# Payload_Computer.net
KiCad netlist of a schematic drawn in EAGLE
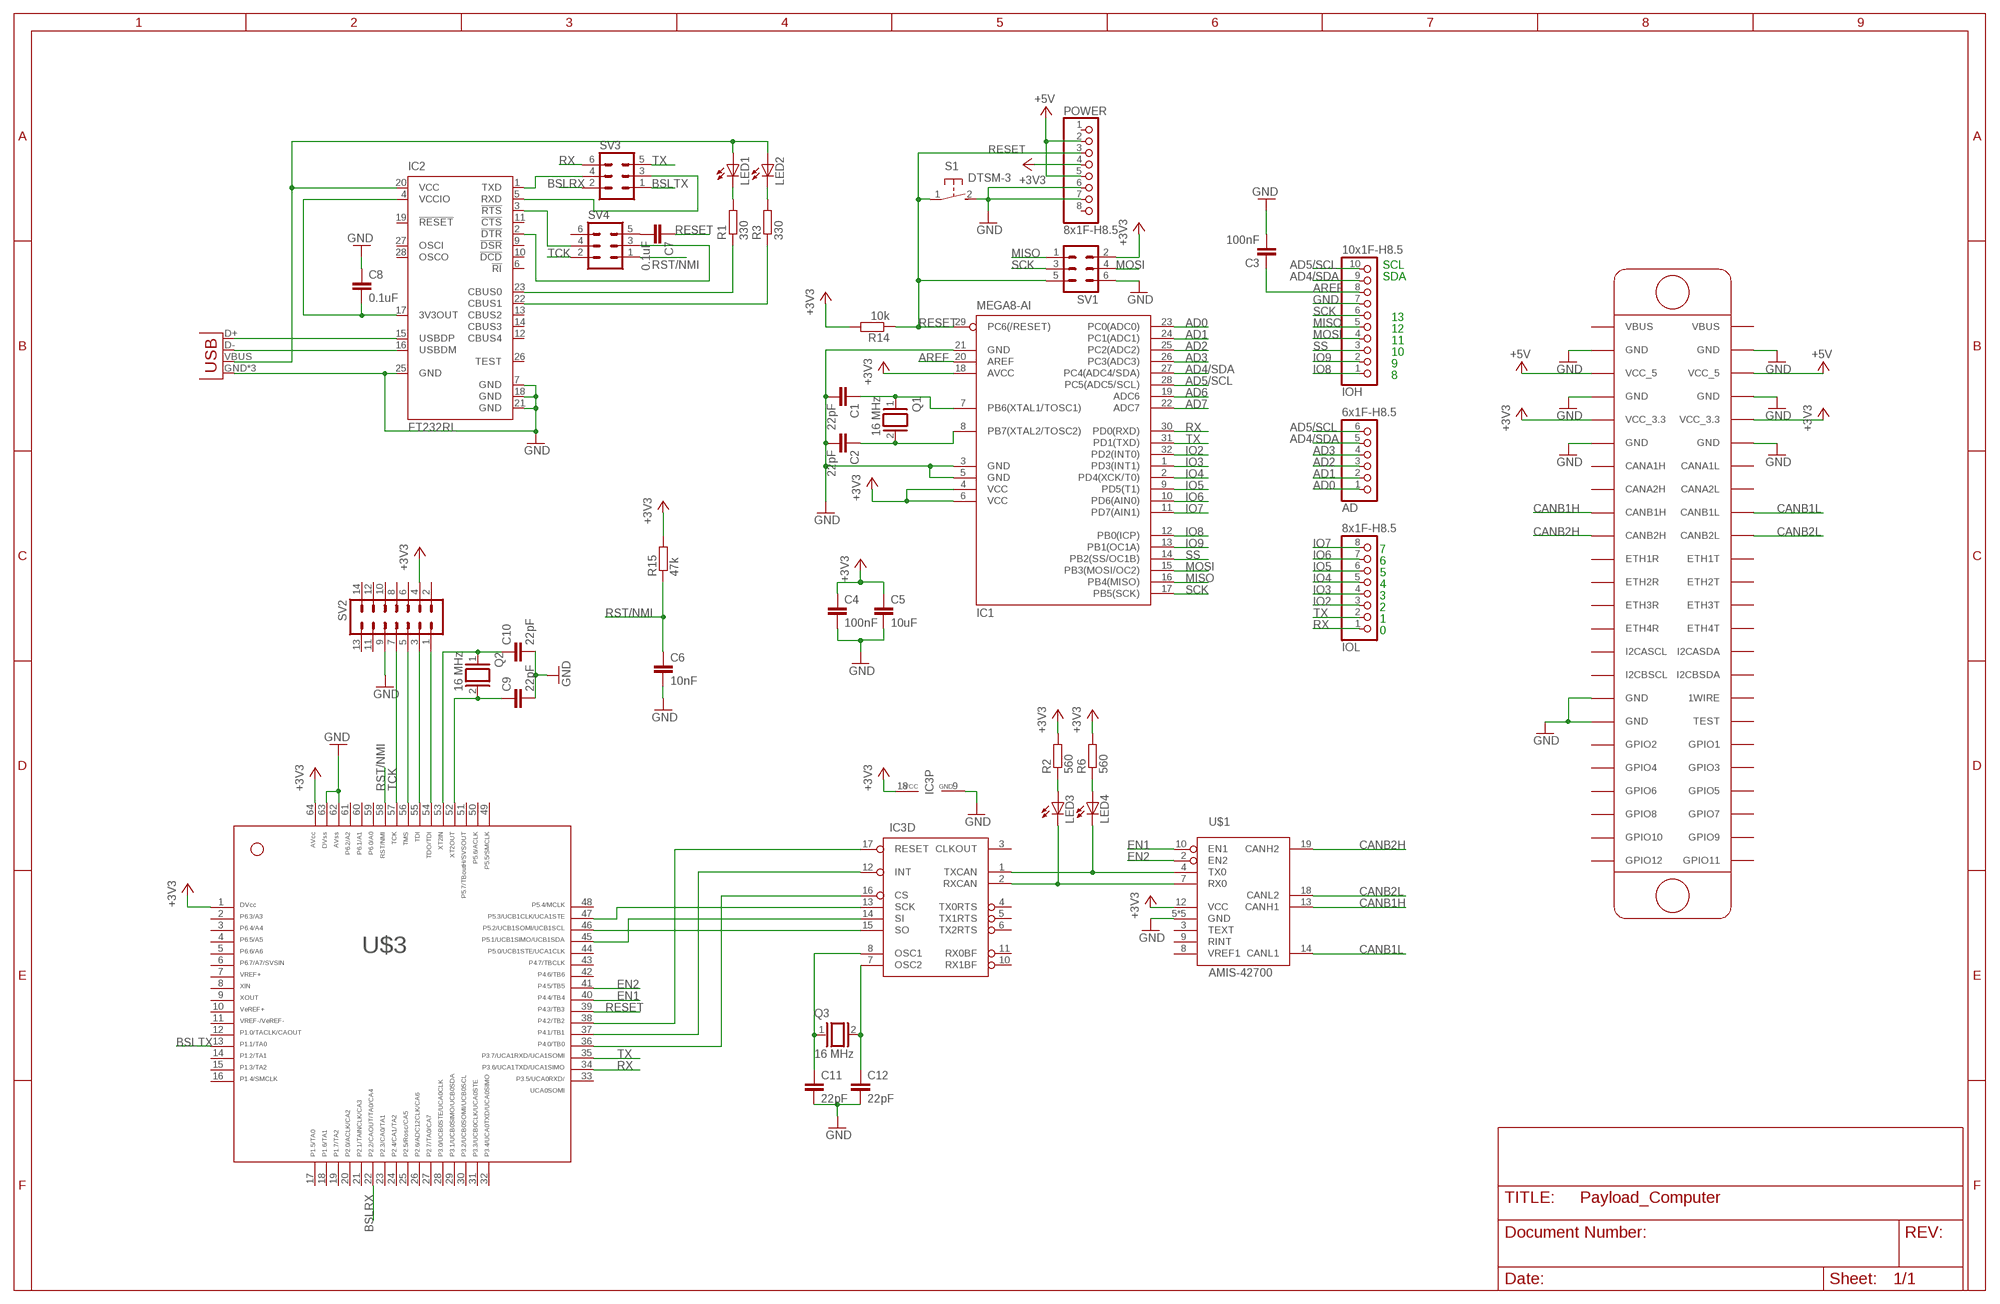
[diagram p0: schematic, sheet 1]

(export (version "E")
  (design (tool "Eeschema 10.0.6"))
  (components
    (comp (ref "AD")
      (value "6x1F-H8.5")
      (footprint "eagle-import:1X06")
      (libsource (lib "eagle-import") (part "PINHD-1X6"))
    )
    (comp (ref "C1")
      (value "22pF")
      (footprint "eagle-import:C0805")
      (libsource (lib "eagle-import") (part "C-EUC0805"))
    )
    (comp (ref "C2")
      (value "22pF")
      (footprint "eagle-import:C0805")
      (libsource (lib "eagle-import") (part "C-EUC0805"))
    )
    (comp (ref "C3")
      (value "100nF")
      (footprint "eagle-import:C0805")
      (libsource (lib "eagle-import") (part "C-EUC0805"))
    )
    (comp (ref "C4")
      (value "100nF")
      (footprint "eagle-import:C0805")
      (libsource (lib "eagle-import") (part "C-EUC0805"))
    )
    (comp (ref "C5")
      (value "10uF")
      (footprint "eagle-import:C0805")
      (libsource (lib "eagle-import") (part "C-EUC0805"))
    )
    (comp (ref "C6")
      (value "10nF")
      (footprint "eagle-import:C0805")
      (libsource (lib "eagle-import") (part "C-EUC0805"))
    )
    (comp (ref "C7")
      (value "0.1uF")
      (footprint "eagle-import:C0805")
      (libsource (lib "eagle-import") (part "C-EUC0805"))
    )
    (comp (ref "C8")
      (value "0.1uF")
      (footprint "eagle-import:C0805")
      (libsource (lib "eagle-import") (part "C-EUC0805"))
    )
    (comp (ref "C9")
      (value "22pF")
      (footprint "eagle-import:C0805")
      (libsource (lib "eagle-import") (part "C-EUC0805"))
    )
    (comp (ref "C10")
      (value "22pF")
      (footprint "eagle-import:C0805")
      (libsource (lib "eagle-import") (part "C-EUC0805"))
    )
    (comp (ref "C11")
      (value "22pF")
      (footprint "eagle-import:C0805")
      (libsource (lib "eagle-import") (part "C-EUC0805"))
    )
    (comp (ref "C12")
      (value "22pF")
      (footprint "eagle-import:C0805")
      (libsource (lib "eagle-import") (part "C-EUC0805"))
    )
    (comp (ref "IC1")
      (value "MEGA8-AI")
      (footprint "eagle-import:TQFP32-08")
      (fields (field (name "MPN") "ATMEGA8-16AU"))
      (libsource (lib "eagle-import") (part "MEGA8-AI"))
    )
    (comp (ref "IC2")
      (value "FT232RL")
      (footprint "eagle-import:SSOP28")
      (libsource (lib "eagle-import") (part "FT232RL"))
    )
    (comp (ref "IC3")
      (value "MCP2515SO")
      (footprint "eagle-import:SO-18W")
      (libsource (lib "eagle-import") (part "MCP2515SO"))
    )
    (comp (ref "IOH")
      (value "10x1F-H8.5")
      (footprint "eagle-import:1X10")
      (libsource (lib "eagle-import") (part "PINHD-1X10_ARD"))
    )
    (comp (ref "IOL")
      (value "8x1F-H8.5")
      (footprint "eagle-import:1X08")
      (libsource (lib "eagle-import") (part "PINHD-1X8"))
    )
    (comp (ref "JP1")
      (value "USB-MICROB")
      (footprint "eagle-import:USB-MICROB")
      (libsource (lib "eagle-import") (part "USB-MICROB"))
    )
    (comp (ref "LED1")
      (value "LED3MM")
      (footprint "eagle-import:LED3MM")
      (libsource (lib "eagle-import") (part "LED3MM"))
    )
    (comp (ref "LED2")
      (value "LED3MM")
      (footprint "eagle-import:LED3MM")
      (libsource (lib "eagle-import") (part "LED3MM"))
    )
    (comp (ref "LED3")
      (value "LED3MM")
      (footprint "eagle-import:LED3MM")
      (libsource (lib "eagle-import") (part "LED3MM"))
    )
    (comp (ref "LED4")
      (value "LED3MM")
      (footprint "eagle-import:LED3MM")
      (libsource (lib "eagle-import") (part "LED3MM"))
    )
    (comp (ref "POWER")
      (value "8x1F-H8.5")
      (footprint "eagle-import:1X08")
      (libsource (lib "eagle-import") (part "PINHD-1X8"))
    )
    (comp (ref "Q1")
      (value "16 MHz")
      (footprint "eagle-import:QS")
      (libsource (lib "eagle-import") (part "XTAL/S"))
    )
    (comp (ref "Q2")
      (value "16 MHz")
      (footprint "eagle-import:QS")
      (libsource (lib "eagle-import") (part "XTAL/S"))
    )
    (comp (ref "Q3")
      (value "16 MHz")
      (footprint "eagle-import:QS")
      (libsource (lib "eagle-import") (part "XTAL/S"))
    )
    (comp (ref "R1")
      (value "330")
      (footprint "eagle-import:R0805")
      (libsource (lib "eagle-import") (part "R-EU_R0805"))
    )
    (comp (ref "R2")
      (value "560")
      (footprint "eagle-import:R0805")
      (libsource (lib "eagle-import") (part "R-EU_R0805"))
    )
    (comp (ref "R3")
      (value "330")
      (footprint "eagle-import:R0805")
      (libsource (lib "eagle-import") (part "R-EU_R0805"))
    )
    (comp (ref "R6")
      (value "560")
      (footprint "eagle-import:R0805")
      (libsource (lib "eagle-import") (part "R-EU_R0805"))
    )
    (comp (ref "R14")
      (value "10k")
      (footprint "eagle-import:R0805")
      (libsource (lib "eagle-import") (part "R-EU_R0805"))
    )
    (comp (ref "R15")
      (value "47k")
      (footprint "eagle-import:R0805")
      (libsource (lib "eagle-import") (part "R-EU_R0805"))
    )
    (comp (ref "S1")
      (value "DTSM-3")
      (footprint "eagle-import:DTSM-3")
      (libsource (lib "eagle-import") (part "DTSM-3"))
    )
    (comp (ref "SV1")
      (value "MA03-2")
      (footprint "eagle-import:MA03-2")
      (libsource (lib "eagle-import") (part "MA03-2"))
    )
    (comp (ref "SV2")
      (value "MA07-2")
      (footprint "eagle-import:MA07-2")
      (libsource (lib "eagle-import") (part "MA07-2"))
    )
    (comp (ref "SV3")
      (value "MA03-2")
      (footprint "eagle-import:MA03-2")
      (libsource (lib "eagle-import") (part "MA03-2"))
    )
    (comp (ref "SV4")
      (value "MA03-2")
      (footprint "eagle-import:MA03-2")
      (libsource (lib "eagle-import") (part "MA03-2"))
    )
    (comp (ref "U$1")
      (value "AMIS-42700")
      (footprint "eagle-import:SOIC20")
      (libsource (lib "eagle-import") (part "AMIS-42700"))
    )
    (comp (ref "U$2")
      (value "CUBESAT_PCB")
      (footprint "eagle-import:CUBESAT_PCB")
      (libsource (lib "eagle-import") (part "CUBESAT_PCB"))
    )
    (comp (ref "U$3")
      (value "F241X---PM64")
      (footprint "eagle-import:PM_PAG64")
      (libsource (lib "eagle-import") (part "F241X---PM64"))
    )
  )
  (nets
    (net (code "1") (name "+3V3") (class "Default")
      (node (ref "C4") (pin "1") (pinfunction "1_1") (pintype "passive"))
      (node (ref "C5") (pin "1") (pinfunction "1_1") (pintype "passive"))
      (node (ref "IC1") (pin "18") (pinfunction "AVCC_18") (pintype "power_in"))
      (node (ref "IC1") (pin "4") (pinfunction "VCC_4") (pintype "power_in"))
      (node (ref "IC1") (pin "6") (pinfunction "VCC_6") (pintype "power_in"))
      (node (ref "IC3") (pin "18") (pinfunction "VCC_18") (pintype "power_in"))
      (node (ref "POWER") (pin "4") (pinfunction "4_4") (pintype "passive"))
      (node (ref "R14") (pin "2") (pinfunction "2_2") (pintype "passive"))
      (node (ref "R15") (pin "2") (pinfunction "2_2") (pintype "passive"))
      (node (ref "R2") (pin "2") (pinfunction "2_2") (pintype "passive"))
      (node (ref "R6") (pin "2") (pinfunction "2_2") (pintype "passive"))
      (node (ref "SV1") (pin "2") (pinfunction "2_2") (pintype "passive"))
      (node (ref "SV2") (pin "4") (pinfunction "4_4") (pintype "passive"))
      (node (ref "U$1") (pin "12") (pinfunction "VCC_12") (pintype "power_in"))
      (node (ref "U$2") (pin "VCC_3.3@1") (pinfunction "VCC_3.3_VCC_3.3@1") (pintype "bidirectional"))
      (node (ref "U$2") (pin "VCC_3.3@2") (pinfunction "VCC_3.3_VCC_3.3@2") (pintype "bidirectional"))
      (node (ref "U$3") (pin "1") (pinfunction "1_1") (pintype "power_in"))
      (node (ref "U$3") (pin "64") (pinfunction "64_64") (pintype "power_in"))
    )
    (net (code "2") (name "+5V") (class "Default")
      (node (ref "POWER") (pin "2") (pinfunction "2_2") (pintype "passive"))
      (node (ref "POWER") (pin "5") (pinfunction "5_5") (pintype "passive"))
      (node (ref "U$2") (pin "VCC_5@1") (pinfunction "VCC_5_VCC_5@1") (pintype "bidirectional"))
      (node (ref "U$2") (pin "VCC_5@2") (pinfunction "VCC_5_VCC_5@2") (pintype "bidirectional"))
    )
    (net (code "3") (name "/AD0") (class "Default")
      (node (ref "AD") (pin "1") (pinfunction "1_1") (pintype "passive"))
      (node (ref "IC1") (pin "23") (pinfunction "PC0(ADC0)_23") (pintype "bidirectional"))
    )
    (net (code "4") (name "/AD1") (class "Default")
      (node (ref "AD") (pin "2") (pinfunction "2_2") (pintype "passive"))
      (node (ref "IC1") (pin "24") (pinfunction "PC1(ADC1)_24") (pintype "bidirectional"))
    )
    (net (code "5") (name "/AD2") (class "Default")
      (node (ref "AD") (pin "3") (pinfunction "3_3") (pintype "passive"))
      (node (ref "IC1") (pin "25") (pinfunction "PC2(ADC2)_25") (pintype "bidirectional"))
    )
    (net (code "6") (name "/AD3") (class "Default")
      (node (ref "AD") (pin "4") (pinfunction "4_4") (pintype "passive"))
      (node (ref "IC1") (pin "26") (pinfunction "PC3(ADC3)_26") (pintype "bidirectional"))
    )
    (net (code "7") (name "/AD4{slash}SDA") (class "Default")
      (node (ref "AD") (pin "5") (pinfunction "5_5") (pintype "passive"))
      (node (ref "IC1") (pin "27") (pinfunction "PC4(ADC4/SDA)_27") (pintype "bidirectional"))
      (node (ref "IOH") (pin "9") (pinfunction "9_9") (pintype "passive"))
    )
    (net (code "8") (name "/AD5{slash}SCL") (class "Default")
      (node (ref "AD") (pin "6") (pinfunction "6_6") (pintype "passive"))
      (node (ref "IC1") (pin "28") (pinfunction "PC5(ADC5/SCL)_28") (pintype "bidirectional"))
      (node (ref "IOH") (pin "10") (pinfunction "10_10") (pintype "passive"))
    )
    (net (code "9") (name "/AD6") (class "Default")
      (node (ref "IC1") (pin "19") (pinfunction "ADC6_19") (pintype "bidirectional"))
    )
    (net (code "10") (name "/AD7") (class "Default")
      (node (ref "IC1") (pin "22") (pinfunction "ADC7_22") (pintype "bidirectional"))
    )
    (net (code "11") (name "/AREF") (class "Default")
      (node (ref "C3") (pin "1") (pinfunction "1_1") (pintype "passive"))
      (node (ref "IC1") (pin "20") (pinfunction "AREF_20") (pintype "passive"))
      (node (ref "IOH") (pin "8") (pinfunction "8_8") (pintype "passive"))
    )
    (net (code "12") (name "/BSLRX") (class "Default")
      (node (ref "SV3") (pin "2") (pinfunction "2_2") (pintype "passive"))
      (node (ref "U$3") (pin "22") (pinfunction "22_22") (pintype "bidirectional"))
    )
    (net (code "13") (name "/BSLTX") (class "Default")
      (node (ref "SV3") (pin "1") (pinfunction "1_1") (pintype "passive"))
      (node (ref "U$3") (pin "13") (pinfunction "13_13") (pintype "bidirectional"))
    )
    (net (code "14") (name "/CANB1H") (class "Default")
      (node (ref "U$1") (pin "13") (pinfunction "CANH1_13") (pintype "output"))
      (node (ref "U$2") (pin "CANB1H") (pinfunction "CANB1H_CANB1H") (pintype "bidirectional"))
    )
    (net (code "15") (name "/CANB1L") (class "Default")
      (node (ref "U$1") (pin "14") (pinfunction "CANL1_14") (pintype "output"))
      (node (ref "U$2") (pin "CANB1L") (pinfunction "CANB1L_CANB1L") (pintype "bidirectional"))
    )
    (net (code "16") (name "/CANB2H") (class "Default")
      (node (ref "U$1") (pin "19") (pinfunction "CANH2_19") (pintype "output"))
      (node (ref "U$2") (pin "CANB2H") (pinfunction "CANB2H_CANB2H") (pintype "bidirectional"))
    )
    (net (code "17") (name "/CANB2L") (class "Default")
      (node (ref "U$1") (pin "18") (pinfunction "CANL2_18") (pintype "output"))
      (node (ref "U$2") (pin "CANB2L") (pinfunction "CANB2L_CANB2L") (pintype "bidirectional"))
    )
    (net (code "18") (name "/EN1") (class "Default")
      (node (ref "U$1") (pin "10") (pinfunction "EN1_10") (pintype "input"))
      (node (ref "U$3") (pin "40") (pinfunction "40_40") (pintype "input"))
    )
    (net (code "19") (name "/EN2") (class "Default")
      (node (ref "U$1") (pin "2") (pinfunction "EN2_2") (pintype "input"))
      (node (ref "U$3") (pin "41") (pinfunction "41_41") (pintype "bidirectional"))
    )
    (net (code "20") (name "/IO2") (class "Default")
      (node (ref "IC1") (pin "32") (pinfunction "PD2(INT0)_32") (pintype "bidirectional"))
      (node (ref "IOL") (pin "3") (pinfunction "3_3") (pintype "passive"))
    )
    (net (code "21") (name "/IO3") (class "Default")
      (node (ref "IC1") (pin "1") (pinfunction "PD3(INT1)_1") (pintype "bidirectional"))
      (node (ref "IOL") (pin "4") (pinfunction "4_4") (pintype "passive"))
    )
    (net (code "22") (name "/IO4") (class "Default")
      (node (ref "IC1") (pin "2") (pinfunction "PD4(XCK/T0)_2") (pintype "bidirectional"))
      (node (ref "IOL") (pin "5") (pinfunction "5_5") (pintype "passive"))
    )
    (net (code "23") (name "/IO5") (class "Default")
      (node (ref "IC1") (pin "9") (pinfunction "PD5(T1)_9") (pintype "bidirectional"))
      (node (ref "IOL") (pin "6") (pinfunction "6_6") (pintype "passive"))
    )
    (net (code "24") (name "/IO6") (class "Default")
      (node (ref "IC1") (pin "10") (pinfunction "PD6(AIN0)_10") (pintype "bidirectional"))
      (node (ref "IOL") (pin "7") (pinfunction "7_7") (pintype "passive"))
    )
    (net (code "25") (name "/IO7") (class "Default")
      (node (ref "IC1") (pin "11") (pinfunction "PD7(AIN1)_11") (pintype "bidirectional"))
      (node (ref "IOL") (pin "8") (pinfunction "8_8") (pintype "passive"))
    )
    (net (code "26") (name "/IO8") (class "Default")
      (node (ref "IC1") (pin "12") (pinfunction "PB0(ICP)_12") (pintype "bidirectional"))
      (node (ref "IOH") (pin "1") (pinfunction "1_1") (pintype "passive"))
    )
    (net (code "27") (name "/IO9") (class "Default")
      (node (ref "IC1") (pin "13") (pinfunction "PB1(OC1A)_13") (pintype "bidirectional"))
      (node (ref "IOH") (pin "2") (pinfunction "2_2") (pintype "passive"))
    )
    (net (code "28") (name "/MISO") (class "Default")
      (node (ref "IC1") (pin "16") (pinfunction "PB4(MISO)_16") (pintype "bidirectional"))
      (node (ref "IOH") (pin "5") (pinfunction "5_5") (pintype "passive"))
      (node (ref "SV1") (pin "1") (pinfunction "1_1") (pintype "passive"))
    )
    (net (code "29") (name "/MOSI") (class "Default")
      (node (ref "IC1") (pin "15") (pinfunction "PB3(MOSI/OC2)_15") (pintype "bidirectional"))
      (node (ref "IOH") (pin "4") (pinfunction "4_4") (pintype "passive"))
      (node (ref "SV1") (pin "4") (pinfunction "4_4") (pintype "passive"))
    )
    (net (code "30") (name "/RESET") (class "Default")
      (node (ref "C7") (pin "1") (pinfunction "1_1") (pintype "passive"))
      (node (ref "IC1") (pin "29") (pinfunction "PC6(/RESET)_29") (pintype "bidirectional"))
      (node (ref "POWER") (pin "3") (pinfunction "3_3") (pintype "passive"))
      (node (ref "R14") (pin "1") (pinfunction "1_1") (pintype "passive"))
      (node (ref "S1") (pin "1") (pinfunction "1_1") (pintype "passive"))
      (node (ref "SV1") (pin "5") (pinfunction "5_5") (pintype "passive"))
      (node (ref "U$3") (pin "39") (pinfunction "39_39") (pintype "bidirectional"))
    )
    (net (code "31") (name "/RST{slash}NMI") (class "Default")
      (node (ref "C6") (pin "1") (pinfunction "1_1") (pintype "passive"))
      (node (ref "R15") (pin "1") (pinfunction "1_1") (pintype "passive"))
      (node (ref "SV4") (pin "1") (pinfunction "1_1") (pintype "passive"))
      (node (ref "U$3") (pin "58") (pinfunction "58_58") (pintype "input"))
    )
    (net (code "32") (name "/RX") (class "Default")
      (node (ref "IC1") (pin "30") (pinfunction "PD0(RXD)_30") (pintype "bidirectional"))
      (node (ref "IOL") (pin "1") (pinfunction "1_1") (pintype "passive"))
      (node (ref "SV3") (pin "6") (pinfunction "6_6") (pintype "passive"))
      (node (ref "U$3") (pin "34") (pinfunction "34_34") (pintype "bidirectional"))
    )
    (net (code "33") (name "/SCK") (class "Default")
      (node (ref "IC1") (pin "17") (pinfunction "PB5(SCK)_17") (pintype "bidirectional"))
      (node (ref "IOH") (pin "6") (pinfunction "6_6") (pintype "passive"))
      (node (ref "SV1") (pin "3") (pinfunction "3_3") (pintype "passive"))
    )
    (net (code "34") (name "/SS") (class "Default")
      (node (ref "IC1") (pin "14") (pinfunction "PB2(SS/OC1B)_14") (pintype "bidirectional"))
      (node (ref "IOH") (pin "3") (pinfunction "3_3") (pintype "passive"))
    )
    (net (code "35") (name "/TCK") (class "Default")
      (node (ref "SV2") (pin "7") (pinfunction "7_7") (pintype "passive"))
      (node (ref "SV4") (pin "2") (pinfunction "2_2") (pintype "passive"))
      (node (ref "U$3") (pin "57") (pinfunction "57_57") (pintype "input"))
    )
    (net (code "36") (name "/TX") (class "Default")
      (node (ref "IC1") (pin "31") (pinfunction "PD1(TXD)_31") (pintype "bidirectional"))
      (node (ref "IOL") (pin "2") (pinfunction "2_2") (pintype "passive"))
      (node (ref "SV3") (pin "5") (pinfunction "5_5") (pintype "passive"))
      (node (ref "U$3") (pin "35") (pinfunction "35_35") (pintype "bidirectional"))
    )
    (net (code "37") (name "GND") (class "Default")
      (node (ref "C1") (pin "2") (pinfunction "2_2") (pintype "passive"))
      (node (ref "C10") (pin "2") (pinfunction "2_2") (pintype "passive"))
      (node (ref "C11") (pin "2") (pinfunction "2_2") (pintype "passive"))
      (node (ref "C12") (pin "2") (pinfunction "2_2") (pintype "passive"))
      (node (ref "C2") (pin "2") (pinfunction "2_2") (pintype "passive"))
      (node (ref "C3") (pin "2") (pinfunction "2_2") (pintype "passive"))
      (node (ref "C4") (pin "2") (pinfunction "2_2") (pintype "passive"))
      (node (ref "C5") (pin "2") (pinfunction "2_2") (pintype "passive"))
      (node (ref "C6") (pin "2") (pinfunction "2_2") (pintype "passive"))
      (node (ref "C8") (pin "1") (pinfunction "1_1") (pintype "passive"))
      (node (ref "C9") (pin "2") (pinfunction "2_2") (pintype "passive"))
      (node (ref "IC1") (pin "21") (pinfunction "GND_21") (pintype "power_in"))
      (node (ref "IC1") (pin "3") (pinfunction "GND_3") (pintype "power_in"))
      (node (ref "IC1") (pin "5") (pinfunction "GND_5") (pintype "power_in"))
      (node (ref "IC2") (pin "18") (pinfunction "GND_18") (pintype "power_in"))
      (node (ref "IC2") (pin "21") (pinfunction "GND_21") (pintype "power_in"))
      (node (ref "IC2") (pin "25") (pinfunction "GND_25") (pintype "power_in"))
      (node (ref "IC2") (pin "7") (pinfunction "GND_7") (pintype "power_in"))
      (node (ref "IC3") (pin "9") (pinfunction "GND_9") (pintype "power_in"))
      (node (ref "IOH") (pin "7") (pinfunction "7_7") (pintype "passive"))
      (node (ref "JP1") (pin "GND") (pinfunction "GND_GND") (pintype "bidirectional"))
      (node (ref "JP1") (pin "MT1") (pinfunction "GND_MT1") (pintype "bidirectional"))
      (node (ref "JP1") (pin "MT2") (pinfunction "GND_MT2") (pintype "bidirectional"))
      (node (ref "POWER") (pin "6") (pinfunction "6_6") (pintype "passive"))
      (node (ref "POWER") (pin "7") (pinfunction "7_7") (pintype "passive"))
      (node (ref "S1") (pin "2") (pinfunction "2_2") (pintype "passive"))
      (node (ref "SV1") (pin "6") (pinfunction "6_6") (pintype "passive"))
      (node (ref "SV2") (pin "9") (pinfunction "9_9") (pintype "passive"))
      (node (ref "U$1") (pin "15") (pinfunction "GND_15") (pintype "input"))
      (node (ref "U$1") (pin "16") (pinfunction "GND_16") (pintype "input"))
      (node (ref "U$1") (pin "17") (pinfunction "GND_17") (pintype "input"))
      (node (ref "U$1") (pin "5") (pinfunction "GND_5") (pintype "input"))
      (node (ref "U$1") (pin "6") (pinfunction "GND_6") (pintype "input"))
      (node (ref "U$2") (pin "GND@10") (pinfunction "GND_GND@10") (pintype "bidirectional"))
      (node (ref "U$2") (pin "GND@11") (pinfunction "GND_GND@11") (pintype "bidirectional"))
      (node (ref "U$2") (pin "GND@12") (pinfunction "GND_GND@12") (pintype "bidirectional"))
      (node (ref "U$2") (pin "GND@5") (pinfunction "GND_GND@5") (pintype "bidirectional"))
      (node (ref "U$2") (pin "GND@6") (pinfunction "GND_GND@6") (pintype "bidirectional"))
      (node (ref "U$2") (pin "GND@7") (pinfunction "GND_GND@7") (pintype "bidirectional"))
      (node (ref "U$2") (pin "GND@8") (pinfunction "GND_GND@8") (pintype "bidirectional"))
      (node (ref "U$2") (pin "GND@9") (pinfunction "GND_GND@9") (pintype "bidirectional"))
      (node (ref "U$3") (pin "62") (pinfunction "62_62") (pintype "power_in"))
      (node (ref "U$3") (pin "63") (pinfunction "63_63") (pintype "power_in"))
    )
    (net (code "38") (name "Net-(C7-Pad2)") (class "Default")
      (node (ref "C7") (pin "2") (pinfunction "2_2") (pintype "passive"))
      (node (ref "SV4") (pin "5") (pinfunction "5_5") (pintype "passive"))
    )
    (net (code "39") (name "Net-(C9-Pad1)") (class "Default")
      (node (ref "C9") (pin "1") (pinfunction "1_1") (pintype "passive"))
      (node (ref "Q2") (pin "2") (pinfunction "2_2") (pintype "passive"))
      (node (ref "U$3") (pin "52") (pinfunction "52_52") (pintype "output"))
    )
    (net (code "40") (name "Net-(C10-Pad1)") (class "Default")
      (node (ref "C10") (pin "1") (pinfunction "1_1") (pintype "passive"))
      (node (ref "Q2") (pin "1") (pinfunction "1_1") (pintype "passive"))
      (node (ref "U$3") (pin "53") (pinfunction "53_53") (pintype "input"))
    )
    (net (code "41") (name "Net-(IC1-PB6(XTAL1{slash}TOSC1))") (class "Default")
      (node (ref "C1") (pin "1") (pinfunction "1_1") (pintype "passive"))
      (node (ref "IC1") (pin "7") (pinfunction "PB6(XTAL1/TOSC1)_7") (pintype "bidirectional"))
      (node (ref "Q1") (pin "1") (pinfunction "1_1") (pintype "passive"))
    )
    (net (code "42") (name "Net-(IC1-PB7(XTAL2{slash}TOSC2))") (class "Default")
      (node (ref "C2") (pin "1") (pinfunction "1_1") (pintype "passive"))
      (node (ref "IC1") (pin "8") (pinfunction "PB7(XTAL2/TOSC2)_8") (pintype "bidirectional"))
      (node (ref "Q1") (pin "2") (pinfunction "2_2") (pintype "passive"))
    )
    (net (code "43") (name "Net-(IC2-3V3OUT)") (class "Default")
      (node (ref "C8") (pin "2") (pinfunction "2_2") (pintype "passive"))
      (node (ref "IC2") (pin "17") (pinfunction "3V3OUT_17") (pintype "output"))
      (node (ref "IC2") (pin "4") (pinfunction "VCCIO_4") (pintype "power_in"))
    )
    (net (code "44") (name "Net-(IC2-CBUS0)") (class "Default")
      (node (ref "IC2") (pin "23") (pinfunction "CBUS0_23") (pintype "bidirectional"))
      (node (ref "R1") (pin "1") (pinfunction "1_1") (pintype "passive"))
    )
    (net (code "45") (name "Net-(IC2-CBUS1)") (class "Default")
      (node (ref "IC2") (pin "22") (pinfunction "CBUS1_22") (pintype "bidirectional"))
      (node (ref "R3") (pin "1") (pinfunction "1_1") (pintype "passive"))
    )
    (net (code "46") (name "Net-(IC2-RXD)") (class "Default")
      (node (ref "IC2") (pin "5") (pinfunction "RXD_5") (pintype "input"))
      (node (ref "SV3") (pin "3") (pinfunction "3_3") (pintype "passive"))
    )
    (net (code "47") (name "Net-(IC2-TXD)") (class "Default")
      (node (ref "IC2") (pin "1") (pinfunction "TXD_1") (pintype "output"))
      (node (ref "SV3") (pin "4") (pinfunction "4_4") (pintype "passive"))
    )
    (net (code "48") (name "Net-(IC2-USBDM)") (class "Default")
      (node (ref "IC2") (pin "16") (pinfunction "USBDM_16") (pintype "bidirectional"))
      (node (ref "JP1") (pin "D-") (pinfunction "D-_D-") (pintype "bidirectional"))
    )
    (net (code "49") (name "Net-(IC2-USBDP)") (class "Default")
      (node (ref "IC2") (pin "15") (pinfunction "USBDP_15") (pintype "bidirectional"))
      (node (ref "JP1") (pin "D+") (pinfunction "D+_D+") (pintype "bidirectional"))
    )
    (net (code "50") (name "Net-(IC2-VCC)") (class "Default")
      (node (ref "IC2") (pin "20") (pinfunction "VCC_20") (pintype "power_in"))
      (node (ref "JP1") (pin "VBUS") (pinfunction "VBUS_VBUS") (pintype "bidirectional"))
      (node (ref "LED1") (pin "A") (pinfunction "A_A") (pintype "passive"))
      (node (ref "LED2") (pin "A") (pinfunction "A_A") (pintype "passive"))
    )
    (net (code "51") (name "Net-(IC2-~{DTR})") (class "Default")
      (node (ref "IC2") (pin "2") (pinfunction "~{DTR}_2") (pintype "output"))
      (node (ref "SV4") (pin "3") (pinfunction "3_3") (pintype "passive"))
    )
    (net (code "52") (name "Net-(IC2-~{RTS})") (class "Default")
      (node (ref "IC2") (pin "3") (pinfunction "~{RTS}_3") (pintype "output"))
      (node (ref "SV4") (pin "4") (pinfunction "4_4") (pintype "passive"))
    )
    (net (code "53") (name "Net-(IC3A-CS)") (class "Default")
      (node (ref "IC3") (pin "16") (pinfunction "CS_16") (pintype "input"))
      (node (ref "U$3") (pin "36") (pinfunction "36_36") (pintype "output"))
    )
    (net (code "54") (name "Net-(IC3A-INT)") (class "Default")
      (node (ref "IC3") (pin "12") (pinfunction "INT_12") (pintype "output"))
      (node (ref "U$3") (pin "37") (pinfunction "37_37") (pintype "bidirectional"))
    )
    (net (code "55") (name "Net-(IC3A-OSC1)") (class "Default")
      (node (ref "C11") (pin "1") (pinfunction "1_1") (pintype "passive"))
      (node (ref "IC3") (pin "8") (pinfunction "OSC1_8") (pintype "input"))
      (node (ref "Q3") (pin "1") (pinfunction "1_1") (pintype "passive"))
    )
    (net (code "56") (name "Net-(IC3A-OSC2)") (class "Default")
      (node (ref "C12") (pin "1") (pinfunction "1_1") (pintype "passive"))
      (node (ref "IC3") (pin "7") (pinfunction "OSC2_7") (pintype "input"))
      (node (ref "Q3") (pin "2") (pinfunction "2_2") (pintype "passive"))
    )
    (net (code "57") (name "Net-(IC3A-RESET)") (class "Default")
      (node (ref "IC3") (pin "17") (pinfunction "RESET_17") (pintype "input"))
      (node (ref "U$3") (pin "38") (pinfunction "38_38") (pintype "bidirectional"))
    )
    (net (code "58") (name "Net-(IC3A-RXCAN)") (class "Default")
      (node (ref "IC3") (pin "2") (pinfunction "RXCAN_2") (pintype "input"))
      (node (ref "LED3") (pin "K") (pinfunction "C_K") (pintype "passive"))
      (node (ref "U$1") (pin "7") (pinfunction "RX0_7") (pintype "input"))
    )
    (net (code "59") (name "Net-(IC3A-SCK)") (class "Default")
      (node (ref "IC3") (pin "13") (pinfunction "SCK_13") (pintype "input"))
      (node (ref "U$3") (pin "47") (pinfunction "47_47") (pintype "bidirectional"))
    )
    (net (code "60") (name "Net-(IC3A-SI)") (class "Default")
      (node (ref "IC3") (pin "14") (pinfunction "SI_14") (pintype "input"))
      (node (ref "U$3") (pin "45") (pinfunction "45_45") (pintype "bidirectional"))
    )
    (net (code "61") (name "Net-(IC3A-SO)") (class "Default")
      (node (ref "IC3") (pin "15") (pinfunction "SO_15") (pintype "output"))
      (node (ref "U$3") (pin "46") (pinfunction "46_46") (pintype "bidirectional"))
    )
    (net (code "62") (name "Net-(IC3A-TXCAN)") (class "Default")
      (node (ref "IC3") (pin "1") (pinfunction "TXCAN_1") (pintype "output"))
      (node (ref "LED4") (pin "K") (pinfunction "C_K") (pintype "passive"))
      (node (ref "U$1") (pin "4") (pinfunction "TX0_4") (pintype "input"))
    )
    (net (code "63") (name "Net-(LED1-C)") (class "Default")
      (node (ref "LED1") (pin "K") (pinfunction "C_K") (pintype "passive"))
      (node (ref "R1") (pin "2") (pinfunction "2_2") (pintype "passive"))
    )
    (net (code "64") (name "Net-(LED2-C)") (class "Default")
      (node (ref "LED2") (pin "K") (pinfunction "C_K") (pintype "passive"))
      (node (ref "R3") (pin "2") (pinfunction "2_2") (pintype "passive"))
    )
    (net (code "65") (name "Net-(LED3-PadA)") (class "Default")
      (node (ref "LED3") (pin "A") (pinfunction "A_A") (pintype "passive"))
      (node (ref "R2") (pin "1") (pinfunction "1_1") (pintype "passive"))
    )
    (net (code "66") (name "Net-(LED4-PadA)") (class "Default")
      (node (ref "LED4") (pin "A") (pinfunction "A_A") (pintype "passive"))
      (node (ref "R6") (pin "1") (pinfunction "1_1") (pintype "passive"))
    )
    (net (code "67") (name "Net-(SV2-Pad1)") (class "Default")
      (node (ref "SV2") (pin "1") (pinfunction "1_1") (pintype "passive"))
      (node (ref "U$3") (pin "54") (pinfunction "54_54") (pintype "bidirectional"))
    )
    (net (code "68") (name "Net-(SV2-Pad3)") (class "Default")
      (node (ref "SV2") (pin "3") (pinfunction "3_3") (pintype "passive"))
      (node (ref "U$3") (pin "55") (pinfunction "55_55") (pintype "input"))
    )
    (net (code "69") (name "Net-(SV2-Pad5)") (class "Default")
      (node (ref "SV2") (pin "5") (pinfunction "5_5") (pintype "passive"))
      (node (ref "U$3") (pin "56") (pinfunction "56_56") (pintype "input"))
    )
    (net (code "70") (name "unconnected-(IC2-CBUS2-Pad13)") (class "Default")
      (node (ref "IC2") (pin "13") (pinfunction "CBUS2_13") (pintype "bidirectional"))
    )
    (net (code "71") (name "unconnected-(IC2-CBUS3-Pad14)") (class "Default")
      (node (ref "IC2") (pin "14") (pinfunction "CBUS3_14") (pintype "bidirectional"))
    )
    (net (code "72") (name "unconnected-(IC2-CBUS4-Pad12)") (class "Default")
      (node (ref "IC2") (pin "12") (pinfunction "CBUS4_12") (pintype "bidirectional"))
    )
    (net (code "73") (name "unconnected-(IC2-OSCI-Pad27)") (class "Default")
      (node (ref "IC2") (pin "27") (pinfunction "OSCI_27") (pintype "input"))
    )
    (net (code "74") (name "unconnected-(IC2-OSCO-Pad28)") (class "Default")
      (node (ref "IC2") (pin "28") (pinfunction "OSCO_28") (pintype "output"))
    )
    (net (code "75") (name "unconnected-(IC2-TEST-Pad26)") (class "Default")
      (node (ref "IC2") (pin "26") (pinfunction "TEST_26") (pintype "input"))
    )
    (net (code "76") (name "unconnected-(IC2-~{CTS}-Pad11)") (class "Default")
      (node (ref "IC2") (pin "11") (pinfunction "~{CTS}_11") (pintype "input"))
    )
    (net (code "77") (name "unconnected-(IC2-~{DCD}-Pad10)") (class "Default")
      (node (ref "IC2") (pin "10") (pinfunction "~{DCD}_10") (pintype "input"))
    )
    (net (code "78") (name "unconnected-(IC2-~{DSR}-Pad9)") (class "Default")
      (node (ref "IC2") (pin "9") (pinfunction "~{DSR}_9") (pintype "input"))
    )
    (net (code "79") (name "unconnected-(IC2-~{RESET}-Pad19)") (class "Default")
      (node (ref "IC2") (pin "19") (pinfunction "~{RESET}_19") (pintype "input"))
    )
    (net (code "80") (name "unconnected-(IC2-~{RI}-Pad6)") (class "Default")
      (node (ref "IC2") (pin "6") (pinfunction "~{RI}_6") (pintype "input"))
    )
    (net (code "81") (name "unconnected-(IC3A-CLKOUT-Pad3)") (class "Default")
      (node (ref "IC3") (pin "3") (pinfunction "CLKOUT_3") (pintype "output"))
    )
    (net (code "82") (name "unconnected-(IC3A-RX0BF-Pad11)") (class "Default")
      (node (ref "IC3") (pin "11") (pinfunction "RX0BF_11") (pintype "output"))
    )
    (net (code "83") (name "unconnected-(IC3A-RX1BF-Pad10)") (class "Default")
      (node (ref "IC3") (pin "10") (pinfunction "RX1BF_10") (pintype "output"))
    )
    (net (code "84") (name "unconnected-(IC3A-TX0RTS-Pad4)") (class "Default")
      (node (ref "IC3") (pin "4") (pinfunction "TX0RTS_4") (pintype "input"))
    )
    (net (code "85") (name "unconnected-(IC3A-TX1RTS-Pad5)") (class "Default")
      (node (ref "IC3") (pin "5") (pinfunction "TX1RTS_5") (pintype "input"))
    )
    (net (code "86") (name "unconnected-(IC3A-TX2RTS-Pad6)") (class "Default")
      (node (ref "IC3") (pin "6") (pinfunction "TX2RTS_6") (pintype "input"))
    )
    (net (code "87") (name "unconnected-(POWER-Pad1)") (class "Default")
      (node (ref "POWER") (pin "1") (pinfunction "1_1") (pintype "passive"))
    )
    (net (code "88") (name "unconnected-(POWER-Pad8)") (class "Default")
      (node (ref "POWER") (pin "8") (pinfunction "8_8") (pintype "passive"))
    )
    (net (code "89") (name "unconnected-(SV2-Pad2)") (class "Default")
      (node (ref "SV2") (pin "2") (pinfunction "2_2") (pintype "passive"))
    )
    (net (code "90") (name "unconnected-(SV2-Pad6)") (class "Default")
      (node (ref "SV2") (pin "6") (pinfunction "6_6") (pintype "passive"))
    )
    (net (code "91") (name "unconnected-(SV2-Pad8)") (class "Default")
      (node (ref "SV2") (pin "8") (pinfunction "8_8") (pintype "passive"))
    )
    (net (code "92") (name "unconnected-(SV2-Pad10)") (class "Default")
      (node (ref "SV2") (pin "10") (pinfunction "10_10") (pintype "passive"))
    )
    (net (code "93") (name "unconnected-(SV2-Pad11)") (class "Default")
      (node (ref "SV2") (pin "11") (pinfunction "11_11") (pintype "passive"))
    )
    (net (code "94") (name "unconnected-(SV2-Pad12)") (class "Default")
      (node (ref "SV2") (pin "12") (pinfunction "12_12") (pintype "passive"))
    )
    (net (code "95") (name "unconnected-(SV2-Pad13)") (class "Default")
      (node (ref "SV2") (pin "13") (pinfunction "13_13") (pintype "passive"))
    )
    (net (code "96") (name "unconnected-(SV2-Pad14)") (class "Default")
      (node (ref "SV2") (pin "14") (pinfunction "14_14") (pintype "passive"))
    )
    (net (code "97") (name "unconnected-(SV4-Pad6)") (class "Default")
      (node (ref "SV4") (pin "6") (pinfunction "6_6") (pintype "passive"))
    )
    (net (code "98") (name "unconnected-(U$1-RINT-Pad9)") (class "Default")
      (node (ref "U$1") (pin "9") (pinfunction "RINT_9") (pintype "input"))
    )
    (net (code "99") (name "unconnected-(U$1-TEXT-Pad3)") (class "Default")
      (node (ref "U$1") (pin "3") (pinfunction "TEXT_3") (pintype "input"))
    )
    (net (code "100") (name "unconnected-(U$1-VREF1-Pad8)") (class "Default")
      (node (ref "U$1") (pin "8") (pinfunction "VREF1_8") (pintype "input"))
    )
    (net (code "101") (name "unconnected-(U$2-Pad1WIRE)") (class "Default")
      (node (ref "U$2") (pin "1WIRE") (pinfunction "1WIRE_1WIRE") (pintype "bidirectional"))
    )
    (net (code "102") (name "unconnected-(U$2-PadCANA1H)") (class "Default")
      (node (ref "U$2") (pin "CANA1H") (pinfunction "CANA1H_CANA1H") (pintype "bidirectional"))
    )
    (net (code "103") (name "unconnected-(U$2-PadCANA1L)") (class "Default")
      (node (ref "U$2") (pin "CANA1L") (pinfunction "CANA1L_CANA1L") (pintype "bidirectional"))
    )
    (net (code "104") (name "unconnected-(U$2-PadCANA2H)") (class "Default")
      (node (ref "U$2") (pin "CANA2H") (pinfunction "CANA2H_CANA2H") (pintype "bidirectional"))
    )
    (net (code "105") (name "unconnected-(U$2-PadCANA2L)") (class "Default")
      (node (ref "U$2") (pin "CANA2L") (pinfunction "CANA2L_CANA2L") (pintype "bidirectional"))
    )
    (net (code "106") (name "unconnected-(U$2-PadETH1R)") (class "Default")
      (node (ref "U$2") (pin "ETH1R") (pinfunction "ETH1R_ETH1R") (pintype "bidirectional"))
    )
    (net (code "107") (name "unconnected-(U$2-PadETH1T)") (class "Default")
      (node (ref "U$2") (pin "ETH1T") (pinfunction "ETH1T_ETH1T") (pintype "bidirectional"))
    )
    (net (code "108") (name "unconnected-(U$2-PadETH2R)") (class "Default")
      (node (ref "U$2") (pin "ETH2R") (pinfunction "ETH2R_ETH2R") (pintype "bidirectional"))
    )
    (net (code "109") (name "unconnected-(U$2-PadETH2T)") (class "Default")
      (node (ref "U$2") (pin "ETH2T") (pinfunction "ETH2T_ETH2T") (pintype "bidirectional"))
    )
    (net (code "110") (name "unconnected-(U$2-PadETH3R)") (class "Default")
      (node (ref "U$2") (pin "ETH3R") (pinfunction "ETH3R_ETH3R") (pintype "bidirectional"))
    )
    (net (code "111") (name "unconnected-(U$2-PadETH3T)") (class "Default")
      (node (ref "U$2") (pin "ETH3T") (pinfunction "ETH3T_ETH3T") (pintype "bidirectional"))
    )
    (net (code "112") (name "unconnected-(U$2-PadETH4R)") (class "Default")
      (node (ref "U$2") (pin "ETH4R") (pinfunction "ETH4R_ETH4R") (pintype "bidirectional"))
    )
    (net (code "113") (name "unconnected-(U$2-PadETH4T)") (class "Default")
      (node (ref "U$2") (pin "ETH4T") (pinfunction "ETH4T_ETH4T") (pintype "bidirectional"))
    )
    (net (code "114") (name "unconnected-(U$2-PadGPIO1)") (class "Default")
      (node (ref "U$2") (pin "GPIO1") (pinfunction "GPIO1_GPIO1") (pintype "bidirectional"))
    )
    (net (code "115") (name "unconnected-(U$2-PadGPIO2)") (class "Default")
      (node (ref "U$2") (pin "GPIO2") (pinfunction "GPIO2_GPIO2") (pintype "bidirectional"))
    )
    (net (code "116") (name "unconnected-(U$2-PadGPIO3)") (class "Default")
      (node (ref "U$2") (pin "GPIO3") (pinfunction "GPIO3_GPIO3") (pintype "bidirectional"))
    )
    (net (code "117") (name "unconnected-(U$2-PadGPIO4)") (class "Default")
      (node (ref "U$2") (pin "GPIO4") (pinfunction "GPIO4_GPIO4") (pintype "bidirectional"))
    )
    (net (code "118") (name "unconnected-(U$2-PadGPIO5)") (class "Default")
      (node (ref "U$2") (pin "GPIO5") (pinfunction "GPIO5_GPIO5") (pintype "bidirectional"))
    )
    (net (code "119") (name "unconnected-(U$2-PadGPIO6)") (class "Default")
      (node (ref "U$2") (pin "GPIO6") (pinfunction "GPIO6_GPIO6") (pintype "bidirectional"))
    )
    (net (code "120") (name "unconnected-(U$2-PadGPIO7)") (class "Default")
      (node (ref "U$2") (pin "GPIO7") (pinfunction "GPIO7_GPIO7") (pintype "bidirectional"))
    )
    (net (code "121") (name "unconnected-(U$2-PadGPIO8)") (class "Default")
      (node (ref "U$2") (pin "GPIO8") (pinfunction "GPIO8_GPIO8") (pintype "bidirectional"))
    )
    (net (code "122") (name "unconnected-(U$2-PadGPIO9)") (class "Default")
      (node (ref "U$2") (pin "GPIO9") (pinfunction "GPIO9_GPIO9") (pintype "bidirectional"))
    )
    (net (code "123") (name "unconnected-(U$2-PadGPIO10)") (class "Default")
      (node (ref "U$2") (pin "GPIO10") (pinfunction "GPIO10_GPIO10") (pintype "bidirectional"))
    )
    (net (code "124") (name "unconnected-(U$2-PadGPIO11)") (class "Default")
      (node (ref "U$2") (pin "GPIO11") (pinfunction "GPIO11_GPIO11") (pintype "bidirectional"))
    )
    (net (code "125") (name "unconnected-(U$2-PadGPIO12)") (class "Default")
      (node (ref "U$2") (pin "GPIO12") (pinfunction "GPIO12_GPIO12") (pintype "bidirectional"))
    )
    (net (code "126") (name "unconnected-(U$2-PadI2CASCL)") (class "Default")
      (node (ref "U$2") (pin "I2CASCL") (pinfunction "I2CASCL_I2CASCL") (pintype "bidirectional"))
    )
    (net (code "127") (name "unconnected-(U$2-PadI2CASDA)") (class "Default")
      (node (ref "U$2") (pin "I2CASDA") (pinfunction "I2CASDA_I2CASDA") (pintype "bidirectional"))
    )
    (net (code "128") (name "unconnected-(U$2-PadI2CBSCL)") (class "Default")
      (node (ref "U$2") (pin "I2CBSCL") (pinfunction "I2CBSCL_I2CBSCL") (pintype "bidirectional"))
    )
    (net (code "129") (name "unconnected-(U$2-PadI2CBSDA)") (class "Default")
      (node (ref "U$2") (pin "I2CBSDA") (pinfunction "I2CBSDA_I2CBSDA") (pintype "bidirectional"))
    )
    (net (code "130") (name "unconnected-(U$2-PadTEST)") (class "Default")
      (node (ref "U$2") (pin "TEST") (pinfunction "TEST_TEST") (pintype "bidirectional"))
    )
    (net (code "131") (name "unconnected-(U$2-VBUS-PadVBUS@1)") (class "Default")
      (node (ref "U$2") (pin "VBUS@1") (pinfunction "VBUS_VBUS@1") (pintype "bidirectional"))
    )
    (net (code "132") (name "unconnected-(U$2-VBUS-PadVBUS@2)") (class "Default")
      (node (ref "U$2") (pin "VBUS@2") (pinfunction "VBUS_VBUS@2") (pintype "bidirectional"))
    )
    (net (code "133") (name "unconnected-(U$3-Pad2)") (class "Default")
      (node (ref "U$3") (pin "2") (pinfunction "2_2") (pintype "bidirectional"))
    )
    (net (code "134") (name "unconnected-(U$3-Pad3)") (class "Default")
      (node (ref "U$3") (pin "3") (pinfunction "3_3") (pintype "bidirectional"))
    )
    (net (code "135") (name "unconnected-(U$3-Pad4)") (class "Default")
      (node (ref "U$3") (pin "4") (pinfunction "4_4") (pintype "bidirectional"))
    )
    (net (code "136") (name "unconnected-(U$3-Pad5)") (class "Default")
      (node (ref "U$3") (pin "5") (pinfunction "5_5") (pintype "bidirectional"))
    )
    (net (code "137") (name "unconnected-(U$3-Pad6)") (class "Default")
      (node (ref "U$3") (pin "6") (pinfunction "6_6") (pintype "bidirectional"))
    )
    (net (code "138") (name "unconnected-(U$3-Pad7)") (class "Default")
      (node (ref "U$3") (pin "7") (pinfunction "7_7") (pintype "output"))
    )
    (net (code "139") (name "unconnected-(U$3-Pad8)") (class "Default")
      (node (ref "U$3") (pin "8") (pinfunction "8_8") (pintype "input"))
    )
    (net (code "140") (name "unconnected-(U$3-Pad9)") (class "Default")
      (node (ref "U$3") (pin "9") (pinfunction "9_9") (pintype "output"))
    )
    (net (code "141") (name "unconnected-(U$3-Pad10)") (class "Default")
      (node (ref "U$3") (pin "10") (pinfunction "10_10") (pintype "bidirectional"))
    )
    (net (code "142") (name "unconnected-(U$3-Pad11)") (class "Default")
      (node (ref "U$3") (pin "11") (pinfunction "11_11") (pintype "bidirectional"))
    )
    (net (code "143") (name "unconnected-(U$3-Pad12)") (class "Default")
      (node (ref "U$3") (pin "12") (pinfunction "12_12") (pintype "bidirectional"))
    )
    (net (code "144") (name "unconnected-(U$3-Pad14)") (class "Default")
      (node (ref "U$3") (pin "14") (pinfunction "14_14") (pintype "bidirectional"))
    )
    (net (code "145") (name "unconnected-(U$3-Pad15)") (class "Default")
      (node (ref "U$3") (pin "15") (pinfunction "15_15") (pintype "bidirectional"))
    )
    (net (code "146") (name "unconnected-(U$3-Pad16)") (class "Default")
      (node (ref "U$3") (pin "16") (pinfunction "16_16") (pintype "bidirectional"))
    )
    (net (code "147") (name "unconnected-(U$3-Pad17)") (class "Default")
      (node (ref "U$3") (pin "17") (pinfunction "17_17") (pintype "bidirectional"))
    )
    (net (code "148") (name "unconnected-(U$3-Pad18)") (class "Default")
      (node (ref "U$3") (pin "18") (pinfunction "18_18") (pintype "bidirectional"))
    )
    (net (code "149") (name "unconnected-(U$3-Pad19)") (class "Default")
      (node (ref "U$3") (pin "19") (pinfunction "19_19") (pintype "bidirectional"))
    )
    (net (code "150") (name "unconnected-(U$3-Pad20)") (class "Default")
      (node (ref "U$3") (pin "20") (pinfunction "20_20") (pintype "bidirectional"))
    )
    (net (code "151") (name "unconnected-(U$3-Pad21)") (class "Default")
      (node (ref "U$3") (pin "21") (pinfunction "21_21") (pintype "bidirectional"))
    )
    (net (code "152") (name "unconnected-(U$3-Pad23)") (class "Default")
      (node (ref "U$3") (pin "23") (pinfunction "23_23") (pintype "bidirectional"))
    )
    (net (code "153") (name "unconnected-(U$3-Pad24)") (class "Default")
      (node (ref "U$3") (pin "24") (pinfunction "24_24") (pintype "bidirectional"))
    )
    (net (code "154") (name "unconnected-(U$3-Pad25)") (class "Default")
      (node (ref "U$3") (pin "25") (pinfunction "25_25") (pintype "bidirectional"))
    )
    (net (code "155") (name "unconnected-(U$3-Pad26)") (class "Default")
      (node (ref "U$3") (pin "26") (pinfunction "26_26") (pintype "bidirectional"))
    )
    (net (code "156") (name "unconnected-(U$3-Pad27)") (class "Default")
      (node (ref "U$3") (pin "27") (pinfunction "27_27") (pintype "bidirectional"))
    )
    (net (code "157") (name "unconnected-(U$3-Pad28)") (class "Default")
      (node (ref "U$3") (pin "28") (pinfunction "28_28") (pintype "bidirectional"))
    )
    (net (code "158") (name "unconnected-(U$3-Pad29)") (class "Default")
      (node (ref "U$3") (pin "29") (pinfunction "29_29") (pintype "bidirectional"))
    )
    (net (code "159") (name "unconnected-(U$3-Pad30)") (class "Default")
      (node (ref "U$3") (pin "30") (pinfunction "30_30") (pintype "bidirectional"))
    )
    (net (code "160") (name "unconnected-(U$3-Pad31)") (class "Default")
      (node (ref "U$3") (pin "31") (pinfunction "31_31") (pintype "bidirectional"))
    )
    (net (code "161") (name "unconnected-(U$3-Pad32)") (class "Default")
      (node (ref "U$3") (pin "32") (pinfunction "32_32") (pintype "bidirectional"))
    )
    (net (code "162") (name "unconnected-(U$3-Pad33)") (class "Default")
      (node (ref "U$3") (pin "33") (pinfunction "33_33") (pintype "bidirectional"))
    )
    (net (code "163") (name "unconnected-(U$3-Pad42)") (class "Default")
      (node (ref "U$3") (pin "42") (pinfunction "42_42") (pintype "bidirectional"))
    )
    (net (code "164") (name "unconnected-(U$3-Pad43)") (class "Default")
      (node (ref "U$3") (pin "43") (pinfunction "43_43") (pintype "bidirectional"))
    )
    (net (code "165") (name "unconnected-(U$3-Pad44)") (class "Default")
      (node (ref "U$3") (pin "44") (pinfunction "44_44") (pintype "bidirectional"))
    )
    (net (code "166") (name "unconnected-(U$3-Pad48)") (class "Default")
      (node (ref "U$3") (pin "48") (pinfunction "48_48") (pintype "bidirectional"))
    )
    (net (code "167") (name "unconnected-(U$3-Pad49)") (class "Default")
      (node (ref "U$3") (pin "49") (pinfunction "49_49") (pintype "bidirectional"))
    )
    (net (code "168") (name "unconnected-(U$3-Pad50)") (class "Default")
      (node (ref "U$3") (pin "50") (pinfunction "50_50") (pintype "bidirectional"))
    )
    (net (code "169") (name "unconnected-(U$3-Pad51)") (class "Default")
      (node (ref "U$3") (pin "51") (pinfunction "51_51") (pintype "bidirectional"))
    )
    (net (code "170") (name "unconnected-(U$3-Pad59)") (class "Default")
      (node (ref "U$3") (pin "59") (pinfunction "59_59") (pintype "bidirectional"))
    )
    (net (code "171") (name "unconnected-(U$3-Pad60)") (class "Default")
      (node (ref "U$3") (pin "60") (pinfunction "60_60") (pintype "bidirectional"))
    )
    (net (code "172") (name "unconnected-(U$3-Pad61)") (class "Default")
      (node (ref "U$3") (pin "61") (pinfunction "61_61") (pintype "bidirectional"))
    )
  )
)
